# My_MucLeo_EXT_Board.net
KiCad netlist of a schematic drawn in Altium Designer
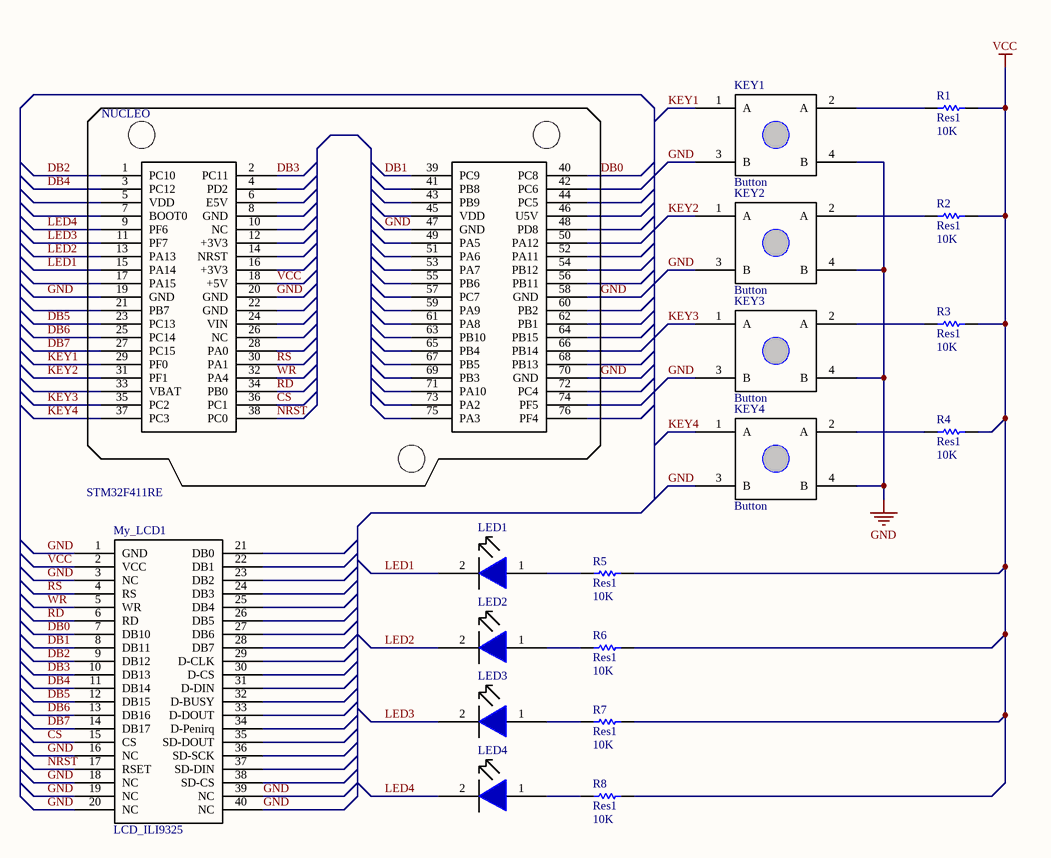
[diagram p0: My_MucLeo_EXT_Board.SchDoc]

(export (version "E")
  (design (tool "Eeschema 10.0.6"))
  (components
    (comp (ref "KEY1")
      (value "Button")
      (footprint "My_Button")
      (description "My Button")
      (libsource (lib "My_Integrated_Library") (part "My_Button"))
    )
    (comp (ref "KEY2")
      (value "Button")
      (footprint "My_Button")
      (description "My Button")
      (libsource (lib "My_Integrated_Library") (part "My_Button"))
    )
    (comp (ref "KEY3")
      (value "Button")
      (footprint "My_Button")
      (description "My Button")
      (libsource (lib "My_Integrated_Library") (part "My_Button"))
    )
    (comp (ref "KEY4")
      (value "Button")
      (footprint "My_Button")
      (description "My Button")
      (libsource (lib "My_Integrated_Library") (part "My_Button"))
    )
    (comp (ref "LED1")
      (value "LED")
      (footprint "LED-F5")
      (description "My LED")
      (libsource (lib "My_Integrated_Library") (part "LED"))
    )
    (comp (ref "LED2")
      (value "LED")
      (footprint "LED-F5")
      (description "My LED")
      (libsource (lib "My_Integrated_Library") (part "LED"))
    )
    (comp (ref "LED3")
      (value "LED")
      (footprint "LED-F5")
      (description "My LED")
      (libsource (lib "My_Integrated_Library") (part "LED"))
    )
    (comp (ref "LED4")
      (value "LED")
      (footprint "LED-F5")
      (description "My LED")
      (libsource (lib "My_Integrated_Library") (part "LED"))
    )
    (comp (ref "My_LCD1")
      (value "LCD_ILI9325")
      (footprint "ILI9325")
      (libsource (lib "My_Schlib") (part "LCD_ILI9325"))
    )
    (comp (ref "NUCLEO")
      (value "STM32F411RE")
      (footprint "NUCLEO Board")
      (description "STM32F411RE Nucleo Board")
      (libsource (lib "My_Integrated_Library") (part "NUCLEO"))
    )
    (comp (ref "R1")
      (value "Res1")
      (footprint "6-0805_N")
      (description "Resistor")
      (fields (field (name "ALTIUM_VALUE") "10K") (field (name "PUBLISHER") "Altium Limited"))
      (libsource (lib "Miscellaneous Devices") (part "Res1"))
    )
    (comp (ref "R2")
      (value "Res1")
      (footprint "6-0805_N")
      (description "Resistor")
      (fields (field (name "ALTIUM_VALUE") "10K") (field (name "PUBLISHER") "Altium Limited"))
      (libsource (lib "Miscellaneous Devices") (part "Res1"))
    )
    (comp (ref "R3")
      (value "Res1")
      (footprint "6-0805_N")
      (description "Resistor")
      (fields (field (name "ALTIUM_VALUE") "10K") (field (name "PUBLISHER") "Altium Limited"))
      (libsource (lib "Miscellaneous Devices") (part "Res1"))
    )
    (comp (ref "R4")
      (value "Res1")
      (footprint "6-0805_N")
      (description "Resistor")
      (fields (field (name "ALTIUM_VALUE") "10K") (field (name "PUBLISHER") "Altium Limited"))
      (libsource (lib "Miscellaneous Devices") (part "Res1"))
    )
    (comp (ref "R5")
      (value "Res1")
      (footprint "6-0805_N")
      (description "Resistor")
      (fields (field (name "ALTIUM_VALUE") "10K") (field (name "PUBLISHER") "Altium Limited"))
      (libsource (lib "Miscellaneous Devices") (part "Res1"))
    )
    (comp (ref "R6")
      (value "Res1")
      (footprint "6-0805_N")
      (description "Resistor")
      (fields (field (name "ALTIUM_VALUE") "10K") (field (name "PUBLISHER") "Altium Limited"))
      (libsource (lib "Miscellaneous Devices") (part "Res1"))
    )
    (comp (ref "R7")
      (value "Res1")
      (footprint "6-0805_N")
      (description "Resistor")
      (fields (field (name "ALTIUM_VALUE") "10K") (field (name "PUBLISHER") "Altium Limited"))
      (libsource (lib "Miscellaneous Devices") (part "Res1"))
    )
    (comp (ref "R8")
      (value "Res1")
      (footprint "6-0805_N")
      (description "Resistor")
      (fields (field (name "ALTIUM_VALUE") "10K") (field (name "PUBLISHER") "Altium Limited"))
      (libsource (lib "Miscellaneous Devices") (part "Res1"))
    )
  )
  (nets
    (net (code "1") (name "/CS") (class "Default")
      (node (ref "My_LCD1") (pin "15") (pinfunction "CS_15") (pintype "passive"))
      (node (ref "NUCLEO") (pin "36") (pinfunction "PC1_36") (pintype "passive"))
    )
    (net (code "2") (name "/DB0") (class "Default")
      (node (ref "My_LCD1") (pin "7") (pinfunction "DB10_7") (pintype "passive"))
      (node (ref "NUCLEO") (pin "40") (pinfunction "PC8_40") (pintype "passive"))
    )
    (net (code "3") (name "/DB1") (class "Default")
      (node (ref "My_LCD1") (pin "8") (pinfunction "DB11_8") (pintype "passive"))
      (node (ref "NUCLEO") (pin "39") (pinfunction "PC9_39") (pintype "passive"))
    )
    (net (code "4") (name "/DB2") (class "Default")
      (node (ref "My_LCD1") (pin "9") (pinfunction "DB12_9") (pintype "passive"))
      (node (ref "NUCLEO") (pin "1") (pinfunction "PC10_1") (pintype "passive"))
    )
    (net (code "5") (name "/DB3") (class "Default")
      (node (ref "My_LCD1") (pin "10") (pinfunction "DB13_10") (pintype "passive"))
      (node (ref "NUCLEO") (pin "2") (pinfunction "PC11_2") (pintype "passive"))
    )
    (net (code "6") (name "/DB4") (class "Default")
      (node (ref "My_LCD1") (pin "11") (pinfunction "DB14_11") (pintype "passive"))
      (node (ref "NUCLEO") (pin "3") (pinfunction "PC12_3") (pintype "passive"))
    )
    (net (code "7") (name "/DB5") (class "Default")
      (node (ref "My_LCD1") (pin "12") (pinfunction "DB15_12") (pintype "passive"))
      (node (ref "NUCLEO") (pin "23") (pinfunction "PC13_23") (pintype "passive"))
    )
    (net (code "8") (name "/DB6") (class "Default")
      (node (ref "My_LCD1") (pin "13") (pinfunction "DB16_13") (pintype "passive"))
      (node (ref "NUCLEO") (pin "25") (pinfunction "PC14_25") (pintype "passive"))
    )
    (net (code "9") (name "/DB7") (class "Default")
      (node (ref "My_LCD1") (pin "14") (pinfunction "DB17_14") (pintype "passive"))
      (node (ref "NUCLEO") (pin "27") (pinfunction "PC15_27") (pintype "passive"))
    )
    (net (code "10") (name "/KEY1") (class "Default")
      (node (ref "KEY1") (pin "1") (pinfunction "A_1") (pintype "passive"))
      (node (ref "NUCLEO") (pin "29") (pinfunction "PF0_29") (pintype "passive"))
    )
    (net (code "11") (name "/KEY2") (class "Default")
      (node (ref "KEY2") (pin "1") (pinfunction "A_1") (pintype "passive"))
      (node (ref "NUCLEO") (pin "31") (pinfunction "PF1_31") (pintype "passive"))
    )
    (net (code "12") (name "/KEY3") (class "Default")
      (node (ref "KEY3") (pin "1") (pinfunction "A_1") (pintype "passive"))
      (node (ref "NUCLEO") (pin "35") (pinfunction "PC2_35") (pintype "passive"))
    )
    (net (code "13") (name "/KEY4") (class "Default")
      (node (ref "KEY4") (pin "1") (pinfunction "A_1") (pintype "passive"))
      (node (ref "NUCLEO") (pin "37") (pinfunction "PC3_37") (pintype "passive"))
    )
    (net (code "14") (name "/LED1") (class "Default")
      (node (ref "LED1") (pin "2") (pinfunction "2_2") (pintype "passive"))
      (node (ref "NUCLEO") (pin "15") (pinfunction "PA14_15") (pintype "passive"))
    )
    (net (code "15") (name "/LED2") (class "Default")
      (node (ref "LED2") (pin "2") (pinfunction "2_2") (pintype "passive"))
      (node (ref "NUCLEO") (pin "13") (pinfunction "PA13_13") (pintype "passive"))
    )
    (net (code "16") (name "/LED3") (class "Default")
      (node (ref "LED3") (pin "2") (pinfunction "2_2") (pintype "passive"))
      (node (ref "NUCLEO") (pin "11") (pinfunction "PF7_11") (pintype "passive"))
    )
    (net (code "17") (name "/LED4") (class "Default")
      (node (ref "LED4") (pin "2") (pinfunction "2_2") (pintype "passive"))
      (node (ref "NUCLEO") (pin "9") (pinfunction "PF6_9") (pintype "passive"))
    )
    (net (code "18") (name "/NRST") (class "Default")
      (node (ref "My_LCD1") (pin "17") (pinfunction "RSET_17") (pintype "passive"))
      (node (ref "NUCLEO") (pin "38") (pinfunction "PC0_38") (pintype "passive"))
    )
    (net (code "19") (name "/RD") (class "Default")
      (node (ref "My_LCD1") (pin "6") (pinfunction "RD_6") (pintype "passive"))
      (node (ref "NUCLEO") (pin "34") (pinfunction "PB0_34") (pintype "passive"))
    )
    (net (code "20") (name "/RS") (class "Default")
      (node (ref "My_LCD1") (pin "4") (pinfunction "RS_4") (pintype "passive"))
      (node (ref "NUCLEO") (pin "30") (pinfunction "PA1_30") (pintype "passive"))
    )
    (net (code "21") (name "/WR") (class "Default")
      (node (ref "My_LCD1") (pin "5") (pinfunction "WR_5") (pintype "passive"))
      (node (ref "NUCLEO") (pin "32") (pinfunction "PA4_32") (pintype "passive"))
    )
    (net (code "22") (name "GND") (class "Default")
      (node (ref "KEY1") (pin "3") (pinfunction "B_3") (pintype "passive"))
      (node (ref "KEY1") (pin "4") (pinfunction "B_4") (pintype "passive"))
      (node (ref "KEY2") (pin "3") (pinfunction "B_3") (pintype "passive"))
      (node (ref "KEY2") (pin "4") (pinfunction "B_4") (pintype "passive"))
      (node (ref "KEY3") (pin "3") (pinfunction "B_3") (pintype "passive"))
      (node (ref "KEY3") (pin "4") (pinfunction "B_4") (pintype "passive"))
      (node (ref "KEY4") (pin "3") (pinfunction "B_3") (pintype "passive"))
      (node (ref "KEY4") (pin "4") (pinfunction "B_4") (pintype "passive"))
      (node (ref "My_LCD1") (pin "1") (pinfunction "GND_1") (pintype "passive"))
      (node (ref "My_LCD1") (pin "16") (pinfunction "NC_16") (pintype "passive"))
      (node (ref "My_LCD1") (pin "18") (pinfunction "NC_18") (pintype "passive"))
      (node (ref "My_LCD1") (pin "19") (pinfunction "NC_19") (pintype "passive"))
      (node (ref "My_LCD1") (pin "20") (pinfunction "NC_20") (pintype "passive"))
      (node (ref "My_LCD1") (pin "3") (pinfunction "NC_3") (pintype "passive"))
      (node (ref "My_LCD1") (pin "39") (pinfunction "NC_39") (pintype "passive"))
      (node (ref "My_LCD1") (pin "40") (pinfunction "NC_40") (pintype "passive"))
      (node (ref "NUCLEO") (pin "19") (pinfunction "GND_19") (pintype "passive"))
      (node (ref "NUCLEO") (pin "20") (pinfunction "GND_20") (pintype "passive"))
      (node (ref "NUCLEO") (pin "47") (pinfunction "GND_47") (pintype "passive"))
      (node (ref "NUCLEO") (pin "58") (pinfunction "GND_58") (pintype "passive"))
      (node (ref "NUCLEO") (pin "70") (pinfunction "GND_70") (pintype "passive"))
    )
    (net (code "23") (name "Net-(KEY1-A-Pad2)") (class "Default")
      (node (ref "KEY1") (pin "2") (pinfunction "A_2") (pintype "passive"))
      (node (ref "R1") (pin "2") (pinfunction "2_2") (pintype "passive"))
    )
    (net (code "24") (name "Net-(KEY2-A-Pad2)") (class "Default")
      (node (ref "KEY2") (pin "2") (pinfunction "A_2") (pintype "passive"))
      (node (ref "R2") (pin "2") (pinfunction "2_2") (pintype "passive"))
    )
    (net (code "25") (name "Net-(KEY3-A-Pad2)") (class "Default")
      (node (ref "KEY3") (pin "2") (pinfunction "A_2") (pintype "passive"))
      (node (ref "R3") (pin "2") (pinfunction "2_2") (pintype "passive"))
    )
    (net (code "26") (name "Net-(KEY4-A-Pad2)") (class "Default")
      (node (ref "KEY4") (pin "2") (pinfunction "A_2") (pintype "passive"))
      (node (ref "R4") (pin "2") (pinfunction "2_2") (pintype "passive"))
    )
    (net (code "27") (name "Net-(LED1-Pad1)") (class "Default")
      (node (ref "LED1") (pin "1") (pinfunction "1_1") (pintype "passive"))
      (node (ref "R5") (pin "2") (pinfunction "2_2") (pintype "passive"))
    )
    (net (code "28") (name "Net-(LED2-Pad1)") (class "Default")
      (node (ref "LED2") (pin "1") (pinfunction "1_1") (pintype "passive"))
      (node (ref "R6") (pin "2") (pinfunction "2_2") (pintype "passive"))
    )
    (net (code "29") (name "Net-(LED3-Pad1)") (class "Default")
      (node (ref "LED3") (pin "1") (pinfunction "1_1") (pintype "passive"))
      (node (ref "R7") (pin "2") (pinfunction "2_2") (pintype "passive"))
    )
    (net (code "30") (name "Net-(LED4-Pad1)") (class "Default")
      (node (ref "LED4") (pin "1") (pinfunction "1_1") (pintype "passive"))
      (node (ref "R8") (pin "2") (pinfunction "2_2") (pintype "passive"))
    )
    (net (code "31") (name "VCC") (class "Default")
      (node (ref "My_LCD1") (pin "2") (pinfunction "VCC_2") (pintype "passive"))
      (node (ref "NUCLEO") (pin "18") (pinfunction "+5V_18") (pintype "passive"))
      (node (ref "R1") (pin "1") (pinfunction "1_1") (pintype "passive"))
      (node (ref "R2") (pin "1") (pinfunction "1_1") (pintype "passive"))
      (node (ref "R3") (pin "1") (pinfunction "1_1") (pintype "passive"))
      (node (ref "R4") (pin "1") (pinfunction "1_1") (pintype "passive"))
      (node (ref "R5") (pin "1") (pinfunction "1_1") (pintype "passive"))
      (node (ref "R6") (pin "1") (pinfunction "1_1") (pintype "passive"))
      (node (ref "R7") (pin "1") (pinfunction "1_1") (pintype "passive"))
      (node (ref "R8") (pin "1") (pinfunction "1_1") (pintype "passive"))
    )
    (net (code "32") (name "unconnected-(My_LCD1-D-BUSY-Pad32)") (class "Default")
      (node (ref "My_LCD1") (pin "32") (pinfunction "D-BUSY_32") (pintype "passive"))
    )
    (net (code "33") (name "unconnected-(My_LCD1-D-CLK-Pad29)") (class "Default")
      (node (ref "My_LCD1") (pin "29") (pinfunction "D-CLK_29") (pintype "passive"))
    )
    (net (code "34") (name "unconnected-(My_LCD1-D-CS-Pad30)") (class "Default")
      (node (ref "My_LCD1") (pin "30") (pinfunction "D-CS_30") (pintype "passive"))
    )
    (net (code "35") (name "unconnected-(My_LCD1-D-DIN-Pad31)") (class "Default")
      (node (ref "My_LCD1") (pin "31") (pinfunction "D-DIN_31") (pintype "passive"))
    )
    (net (code "36") (name "unconnected-(My_LCD1-D-DOUT-Pad33)") (class "Default")
      (node (ref "My_LCD1") (pin "33") (pinfunction "D-DOUT_33") (pintype "passive"))
    )
    (net (code "37") (name "unconnected-(My_LCD1-D-Penirq-Pad34)") (class "Default")
      (node (ref "My_LCD1") (pin "34") (pinfunction "D-Penirq_34") (pintype "passive"))
    )
    (net (code "38") (name "unconnected-(My_LCD1-DB0-Pad21)") (class "Default")
      (node (ref "My_LCD1") (pin "21") (pinfunction "DB0_21") (pintype "passive"))
    )
    (net (code "39") (name "unconnected-(My_LCD1-DB1-Pad22)") (class "Default")
      (node (ref "My_LCD1") (pin "22") (pinfunction "DB1_22") (pintype "passive"))
    )
    (net (code "40") (name "unconnected-(My_LCD1-DB2-Pad23)") (class "Default")
      (node (ref "My_LCD1") (pin "23") (pinfunction "DB2_23") (pintype "passive"))
    )
    (net (code "41") (name "unconnected-(My_LCD1-DB3-Pad24)") (class "Default")
      (node (ref "My_LCD1") (pin "24") (pinfunction "DB3_24") (pintype "passive"))
    )
    (net (code "42") (name "unconnected-(My_LCD1-DB4-Pad25)") (class "Default")
      (node (ref "My_LCD1") (pin "25") (pinfunction "DB4_25") (pintype "passive"))
    )
    (net (code "43") (name "unconnected-(My_LCD1-DB5-Pad26)") (class "Default")
      (node (ref "My_LCD1") (pin "26") (pinfunction "DB5_26") (pintype "passive"))
    )
    (net (code "44") (name "unconnected-(My_LCD1-DB6-Pad27)") (class "Default")
      (node (ref "My_LCD1") (pin "27") (pinfunction "DB6_27") (pintype "passive"))
    )
    (net (code "45") (name "unconnected-(My_LCD1-DB7-Pad28)") (class "Default")
      (node (ref "My_LCD1") (pin "28") (pinfunction "DB7_28") (pintype "passive"))
    )
    (net (code "46") (name "unconnected-(My_LCD1-SD-CS-Pad38)") (class "Default")
      (node (ref "My_LCD1") (pin "38") (pinfunction "SD-CS_38") (pintype "passive"))
    )
    (net (code "47") (name "unconnected-(My_LCD1-SD-DIN-Pad37)") (class "Default")
      (node (ref "My_LCD1") (pin "37") (pinfunction "SD-DIN_37") (pintype "passive"))
    )
    (net (code "48") (name "unconnected-(My_LCD1-SD-DOUT-Pad35)") (class "Default")
      (node (ref "My_LCD1") (pin "35") (pinfunction "SD-DOUT_35") (pintype "passive"))
    )
    (net (code "49") (name "unconnected-(My_LCD1-SD-SCK-Pad36)") (class "Default")
      (node (ref "My_LCD1") (pin "36") (pinfunction "SD-SCK_36") (pintype "passive"))
    )
    (net (code "50") (name "unconnected-(NUCLEO-+3V3-Pad12)") (class "Default")
      (node (ref "NUCLEO") (pin "12") (pinfunction "+3V3_12") (pintype "passive"))
    )
    (net (code "51") (name "unconnected-(NUCLEO-+3V3-Pad16)") (class "Default")
      (node (ref "NUCLEO") (pin "16") (pinfunction "+3V3_16") (pintype "passive"))
    )
    (net (code "52") (name "unconnected-(NUCLEO-BOOT0-Pad7)") (class "Default")
      (node (ref "NUCLEO") (pin "7") (pinfunction "BOOT0_7") (pintype "passive"))
    )
    (net (code "53") (name "unconnected-(NUCLEO-E5V-Pad6)") (class "Default")
      (node (ref "NUCLEO") (pin "6") (pinfunction "E5V_6") (pintype "passive"))
    )
    (net (code "54") (name "unconnected-(NUCLEO-GND-Pad8)") (class "Default")
      (node (ref "NUCLEO") (pin "8") (pinfunction "GND_8") (pintype "passive"))
    )
    (net (code "55") (name "unconnected-(NUCLEO-GND-Pad22)") (class "Default")
      (node (ref "NUCLEO") (pin "22") (pinfunction "GND_22") (pintype "passive"))
    )
    (net (code "56") (name "unconnected-(NUCLEO-NC-Pad10)") (class "Default")
      (node (ref "NUCLEO") (pin "10") (pinfunction "NC_10") (pintype "passive"))
    )
    (net (code "57") (name "unconnected-(NUCLEO-NC-Pad26)") (class "Default")
      (node (ref "NUCLEO") (pin "26") (pinfunction "NC_26") (pintype "passive"))
    )
    (net (code "58") (name "unconnected-(NUCLEO-NRST-Pad14)") (class "Default")
      (node (ref "NUCLEO") (pin "14") (pinfunction "NRST_14") (pintype "passive"))
    )
    (net (code "59") (name "unconnected-(NUCLEO-PA0-Pad28)") (class "Default")
      (node (ref "NUCLEO") (pin "28") (pinfunction "PA0_28") (pintype "passive"))
    )
    (net (code "60") (name "unconnected-(NUCLEO-PA2-Pad73)") (class "Default")
      (node (ref "NUCLEO") (pin "73") (pinfunction "PA2_73") (pintype "passive"))
    )
    (net (code "61") (name "unconnected-(NUCLEO-PA3-Pad75)") (class "Default")
      (node (ref "NUCLEO") (pin "75") (pinfunction "PA3_75") (pintype "passive"))
    )
    (net (code "62") (name "unconnected-(NUCLEO-PA5-Pad49)") (class "Default")
      (node (ref "NUCLEO") (pin "49") (pinfunction "PA5_49") (pintype "passive"))
    )
    (net (code "63") (name "unconnected-(NUCLEO-PA6-Pad51)") (class "Default")
      (node (ref "NUCLEO") (pin "51") (pinfunction "PA6_51") (pintype "passive"))
    )
    (net (code "64") (name "unconnected-(NUCLEO-PA7-Pad53)") (class "Default")
      (node (ref "NUCLEO") (pin "53") (pinfunction "PA7_53") (pintype "passive"))
    )
    (net (code "65") (name "unconnected-(NUCLEO-PA8-Pad61)") (class "Default")
      (node (ref "NUCLEO") (pin "61") (pinfunction "PA8_61") (pintype "passive"))
    )
    (net (code "66") (name "unconnected-(NUCLEO-PA9-Pad59)") (class "Default")
      (node (ref "NUCLEO") (pin "59") (pinfunction "PA9_59") (pintype "passive"))
    )
    (net (code "67") (name "unconnected-(NUCLEO-PA10-Pad71)") (class "Default")
      (node (ref "NUCLEO") (pin "71") (pinfunction "PA10_71") (pintype "passive"))
    )
    (net (code "68") (name "unconnected-(NUCLEO-PA11-Pad52)") (class "Default")
      (node (ref "NUCLEO") (pin "52") (pinfunction "PA11_52") (pintype "passive"))
    )
    (net (code "69") (name "unconnected-(NUCLEO-PA12-Pad50)") (class "Default")
      (node (ref "NUCLEO") (pin "50") (pinfunction "PA12_50") (pintype "passive"))
    )
    (net (code "70") (name "unconnected-(NUCLEO-PA15-Pad17)") (class "Default")
      (node (ref "NUCLEO") (pin "17") (pinfunction "PA15_17") (pintype "passive"))
    )
    (net (code "71") (name "unconnected-(NUCLEO-PB1-Pad62)") (class "Default")
      (node (ref "NUCLEO") (pin "62") (pinfunction "PB1_62") (pintype "passive"))
    )
    (net (code "72") (name "unconnected-(NUCLEO-PB2-Pad60)") (class "Default")
      (node (ref "NUCLEO") (pin "60") (pinfunction "PB2_60") (pintype "passive"))
    )
    (net (code "73") (name "unconnected-(NUCLEO-PB3-Pad69)") (class "Default")
      (node (ref "NUCLEO") (pin "69") (pinfunction "PB3_69") (pintype "passive"))
    )
    (net (code "74") (name "unconnected-(NUCLEO-PB4-Pad65)") (class "Default")
      (node (ref "NUCLEO") (pin "65") (pinfunction "PB4_65") (pintype "passive"))
    )
    (net (code "75") (name "unconnected-(NUCLEO-PB5-Pad67)") (class "Default")
      (node (ref "NUCLEO") (pin "67") (pinfunction "PB5_67") (pintype "passive"))
    )
    (net (code "76") (name "unconnected-(NUCLEO-PB6-Pad55)") (class "Default")
      (node (ref "NUCLEO") (pin "55") (pinfunction "PB6_55") (pintype "passive"))
    )
    (net (code "77") (name "unconnected-(NUCLEO-PB7-Pad21)") (class "Default")
      (node (ref "NUCLEO") (pin "21") (pinfunction "PB7_21") (pintype "passive"))
    )
    (net (code "78") (name "unconnected-(NUCLEO-PB8-Pad41)") (class "Default")
      (node (ref "NUCLEO") (pin "41") (pinfunction "PB8_41") (pintype "passive"))
    )
    (net (code "79") (name "unconnected-(NUCLEO-PB9-Pad43)") (class "Default")
      (node (ref "NUCLEO") (pin "43") (pinfunction "PB9_43") (pintype "passive"))
    )
    (net (code "80") (name "unconnected-(NUCLEO-PB10-Pad63)") (class "Default")
      (node (ref "NUCLEO") (pin "63") (pinfunction "PB10_63") (pintype "passive"))
    )
    (net (code "81") (name "unconnected-(NUCLEO-PB11-Pad56)") (class "Default")
      (node (ref "NUCLEO") (pin "56") (pinfunction "PB11_56") (pintype "passive"))
    )
    (net (code "82") (name "unconnected-(NUCLEO-PB12-Pad54)") (class "Default")
      (node (ref "NUCLEO") (pin "54") (pinfunction "PB12_54") (pintype "passive"))
    )
    (net (code "83") (name "unconnected-(NUCLEO-PB13-Pad68)") (class "Default")
      (node (ref "NUCLEO") (pin "68") (pinfunction "PB13_68") (pintype "passive"))
    )
    (net (code "84") (name "unconnected-(NUCLEO-PB14-Pad66)") (class "Default")
      (node (ref "NUCLEO") (pin "66") (pinfunction "PB14_66") (pintype "passive"))
    )
    (net (code "85") (name "unconnected-(NUCLEO-PB15-Pad64)") (class "Default")
      (node (ref "NUCLEO") (pin "64") (pinfunction "PB15_64") (pintype "passive"))
    )
    (net (code "86") (name "unconnected-(NUCLEO-PC4-Pad72)") (class "Default")
      (node (ref "NUCLEO") (pin "72") (pinfunction "PC4_72") (pintype "passive"))
    )
    (net (code "87") (name "unconnected-(NUCLEO-PC5-Pad44)") (class "Default")
      (node (ref "NUCLEO") (pin "44") (pinfunction "PC5_44") (pintype "passive"))
    )
    (net (code "88") (name "unconnected-(NUCLEO-PC6-Pad42)") (class "Default")
      (node (ref "NUCLEO") (pin "42") (pinfunction "PC6_42") (pintype "passive"))
    )
    (net (code "89") (name "unconnected-(NUCLEO-PC7-Pad57)") (class "Default")
      (node (ref "NUCLEO") (pin "57") (pinfunction "PC7_57") (pintype "passive"))
    )
    (net (code "90") (name "unconnected-(NUCLEO-PD2-Pad4)") (class "Default")
      (node (ref "NUCLEO") (pin "4") (pinfunction "PD2_4") (pintype "passive"))
    )
    (net (code "91") (name "unconnected-(NUCLEO-PD8-Pad48)") (class "Default")
      (node (ref "NUCLEO") (pin "48") (pinfunction "PD8_48") (pintype "passive"))
    )
    (net (code "92") (name "unconnected-(NUCLEO-PF4-Pad76)") (class "Default")
      (node (ref "NUCLEO") (pin "76") (pinfunction "PF4_76") (pintype "passive"))
    )
    (net (code "93") (name "unconnected-(NUCLEO-PF5-Pad74)") (class "Default")
      (node (ref "NUCLEO") (pin "74") (pinfunction "PF5_74") (pintype "passive"))
    )
    (net (code "94") (name "unconnected-(NUCLEO-U5V-Pad46)") (class "Default")
      (node (ref "NUCLEO") (pin "46") (pinfunction "U5V_46") (pintype "passive"))
    )
    (net (code "95") (name "unconnected-(NUCLEO-VBAT-Pad33)") (class "Default")
      (node (ref "NUCLEO") (pin "33") (pinfunction "VBAT_33") (pintype "passive"))
    )
    (net (code "96") (name "unconnected-(NUCLEO-VDD-Pad5)") (class "Default")
      (node (ref "NUCLEO") (pin "5") (pinfunction "VDD_5") (pintype "passive"))
    )
    (net (code "97") (name "unconnected-(NUCLEO-VDD-Pad45)") (class "Default")
      (node (ref "NUCLEO") (pin "45") (pinfunction "VDD_45") (pintype "passive"))
    )
    (net (code "98") (name "unconnected-(NUCLEO-VIN-Pad24)") (class "Default")
      (node (ref "NUCLEO") (pin "24") (pinfunction "VIN_24") (pintype "passive"))
    )
  )
)
